# Sheet1.net
KiCad netlist of a schematic drawn in Altium Designer
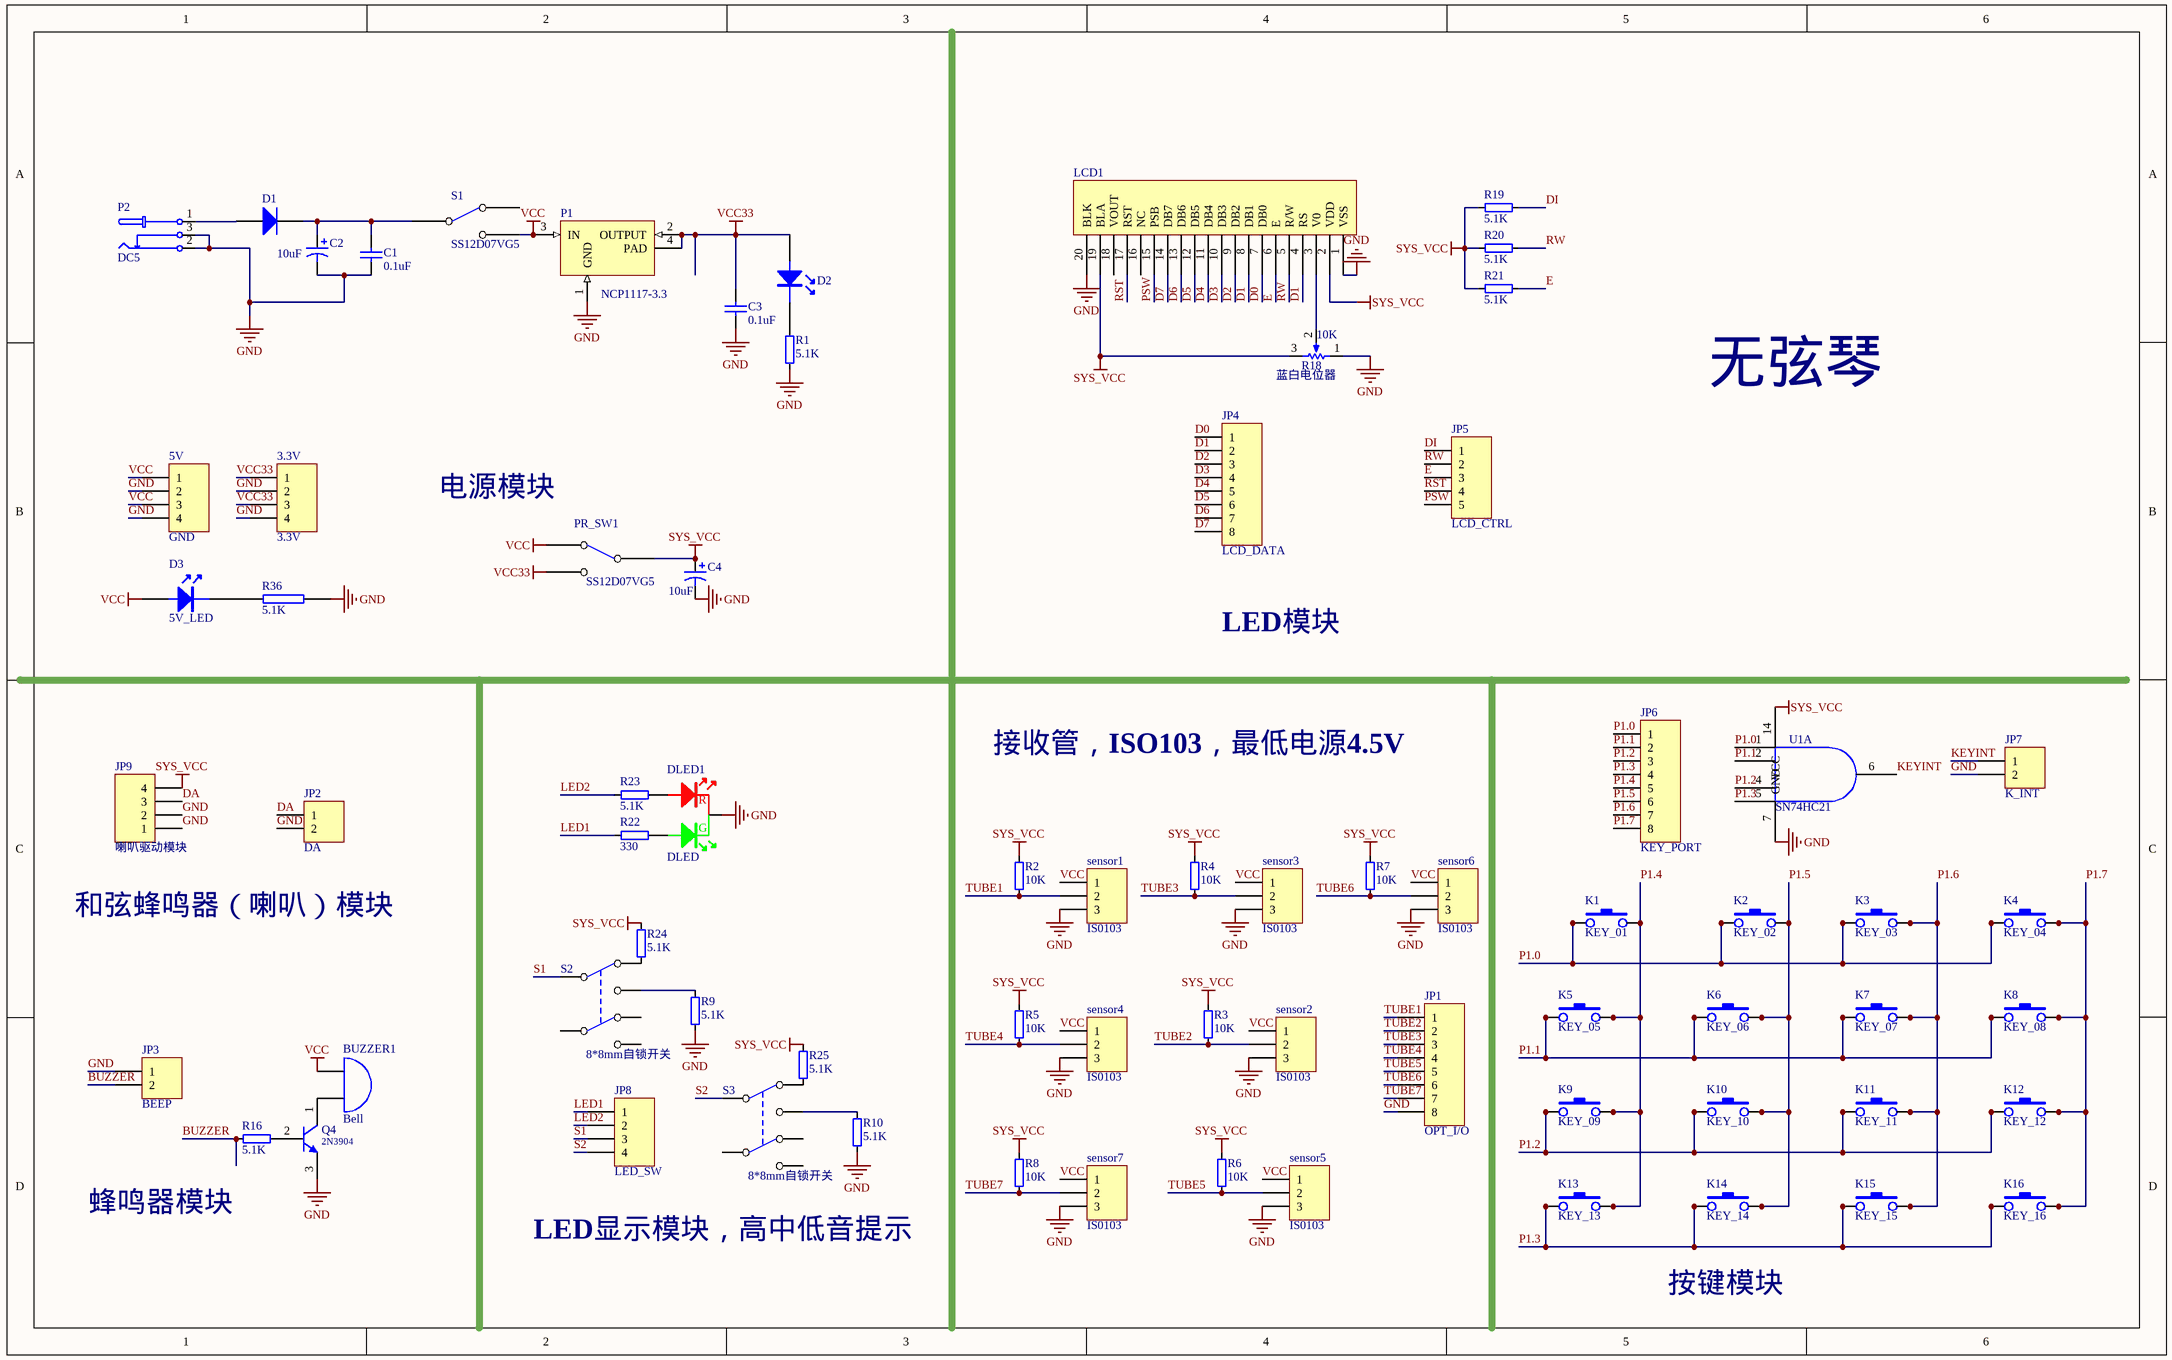
[diagram p0: Sheet1.SchDoc]

(export (version "E")
  (design (tool "Eeschema 10.0.6"))
  (components
    (comp (ref "3.3V")
      (value "3.3V")
      (footprint "HDR1X4")
      (description "Header, 4-Pin")
      (fields (field (name "PUBLISHER") "Altium Limited"))
      (libsource (lib "4. WXQv4") (part "Header 4"))
    )
    (comp (ref "5V")
      (value "GND")
      (footprint "HDR1X4")
      (description "Header, 4-Pin, Right Angle")
      (fields (field (name "PUBLISHER") "Altium Limited"))
      (libsource (lib "4. WXQv4") (part "Header 4H"))
    )
    (comp (ref "BUZZER1")
      (value "Bell")
      (footprint "BUZZER")
      (description "Electrical Bell")
      (fields (field (name "PUBLISHER") "Altium Limited"))
      (libsource (lib "4. WXQv4") (part "Bell"))
    )
    (comp (ref "C1")
      (value "0.1uF")
      (footprint "0805C")
      (description "Capacitor")
      (fields (field (name "PUBLISHER") "Altium Limited"))
      (libsource (lib "4. WXQv4") (part "Cap"))
    )
    (comp (ref "C2")
      (value "10uF")
      (footprint "1206C")
      (description "Polarized Capacitor (Radial)")
      (fields (field (name "PUBLISHER") "Altium Limited"))
      (libsource (lib "4. WXQv4") (part "Cap Pol1"))
    )
    (comp (ref "C3")
      (value "0.1uF")
      (footprint "0805C")
      (description "Capacitor")
      (fields (field (name "PUBLISHER") "Altium Limited"))
      (libsource (lib "4. WXQv4") (part "Cap"))
    )
    (comp (ref "C4")
      (value "10uF")
      (footprint "1206C")
      (description "Polarized Capacitor (Radial)")
      (fields (field (name "PUBLISHER") "Altium Limited"))
      (libsource (lib "4. WXQv4") (part "Cap Pol1"))
    )
    (comp (ref "D1")
      (value "1N4147")
      (footprint "DIODE0.3")
      (description "1 Amp General Purpose Rectifier")
      (fields (field (name "PUBLISHER") "Altium Limited"))
      (libsource (lib "4. WXQv4") (part "Diode 1N4007"))
    )
    (comp (ref "D2") (value "3.3V_LED") (footprint "LED0805") (libsource (lib "4. WXQv4") (part "LED_1")))
    (comp (ref "D3") (value "5V_LED") (footprint "LED0805") (libsource (lib "4. WXQv4") (part "LED_1")))
    (comp (ref "DLED1") (value "DLED") (footprint "DColor LED") (libsource (lib "4. WXQv4") (part "DLED")))
    (comp (ref "JP1")
      (value "OPT_I/O")
      (footprint "HDR1X8")
      (description "Header, 8-Pin")
      (fields (field (name "PUBLISHER") "Altium Limited"))
      (libsource (lib "4. WXQv4") (part "Header 8"))
    )
    (comp (ref "JP2")
      (value "DA")
      (footprint "HDR1X2")
      (description "Header, 2-Pin")
      (fields (field (name "PUBLISHER") "Altium Limited"))
      (libsource (lib "4. WXQv4") (part "Header 2"))
    )
    (comp (ref "JP3")
      (value "BEEP")
      (footprint "HDR1X2")
      (description "Header, 2-Pin")
      (fields (field (name "PUBLISHER") "Altium Limited"))
      (libsource (lib "4. WXQv4") (part "Header 2"))
    )
    (comp (ref "JP4")
      (value "LCD_DATA")
      (footprint "HDR1X8")
      (description "Header, 8-Pin")
      (fields (field (name "PUBLISHER") "Altium Limited"))
      (libsource (lib "4. WXQv4") (part "Header 8"))
    )
    (comp (ref "JP5")
      (value "LCD_CTRL")
      (footprint "HDR1X5")
      (description "Header, 5-Pin")
      (fields (field (name "PUBLISHER") "Altium Limited"))
      (libsource (lib "4. WXQv4") (part "Header 5"))
    )
    (comp (ref "JP6")
      (value "KEY_PORT")
      (footprint "HDR1X8")
      (description "Header, 8-Pin")
      (fields (field (name "PUBLISHER") "Altium Limited"))
      (libsource (lib "4. WXQv4") (part "Header 8"))
    )
    (comp (ref "JP7")
      (value "K_INT")
      (footprint "HDR1X2")
      (description "Header, 2-Pin, Right Angle")
      (fields (field (name "PUBLISHER") "Altium Limited"))
      (libsource (lib "4. WXQv4") (part "Header 2H"))
    )
    (comp (ref "JP8")
      (value "LED_SW")
      (footprint "HDR1X4")
      (description "Header, 4-Pin")
      (fields (field (name "PUBLISHER") "Altium Limited"))
      (libsource (lib "4. WXQv4") (part "Header 4"))
    )
    (comp (ref "JP9")
      (value "喇叭驱动模块")
      (footprint "HDR1X4")
      (description "Header, 4-Pin")
      (fields (field (name "PUBLISHER") "Altium Limited"))
      (libsource (lib "") (part "Header 4_1"))
    )
    (comp (ref "K1")
      (value "KEY_01")
      (footprint "DIP-6X6X5")
      (description "B3F-1055")
      (libsource (lib "4. WXQv4") (part "KEY"))
    )
    (comp (ref "K2")
      (value "KEY_02")
      (footprint "DIP-6X6X5")
      (description "B3F-1055")
      (libsource (lib "4. WXQv4") (part "KEY"))
    )
    (comp (ref "K3")
      (value "KEY_03")
      (footprint "DIP-6X6X5")
      (description "B3F-1055")
      (libsource (lib "4. WXQv4") (part "KEY"))
    )
    (comp (ref "K4")
      (value "KEY_04")
      (footprint "DIP-6X6X5")
      (description "B3F-1055")
      (libsource (lib "4. WXQv4") (part "KEY"))
    )
    (comp (ref "K5")
      (value "KEY_05")
      (footprint "DIP-6X6X5")
      (description "B3F-1055")
      (libsource (lib "4. WXQv4") (part "KEY"))
    )
    (comp (ref "K6")
      (value "KEY_06")
      (footprint "DIP-6X6X5")
      (description "B3F-1055")
      (libsource (lib "4. WXQv4") (part "KEY"))
    )
    (comp (ref "K7")
      (value "KEY_07")
      (footprint "DIP-6X6X5")
      (description "B3F-1055")
      (libsource (lib "4. WXQv4") (part "KEY"))
    )
    (comp (ref "K8")
      (value "KEY_08")
      (footprint "DIP-6X6X5")
      (description "B3F-1055")
      (libsource (lib "4. WXQv4") (part "KEY"))
    )
    (comp (ref "K9")
      (value "KEY_09")
      (footprint "DIP-6X6X5")
      (description "B3F-1055")
      (libsource (lib "4. WXQv4") (part "KEY"))
    )
    (comp (ref "K10")
      (value "KEY_10")
      (footprint "DIP-6X6X5")
      (description "B3F-1055")
      (libsource (lib "4. WXQv4") (part "KEY"))
    )
    (comp (ref "K11")
      (value "KEY_11")
      (footprint "DIP-6X6X5")
      (description "B3F-1055")
      (libsource (lib "4. WXQv4") (part "KEY"))
    )
    (comp (ref "K12")
      (value "KEY_12")
      (footprint "DIP-6X6X5")
      (description "B3F-1055")
      (libsource (lib "4. WXQv4") (part "KEY"))
    )
    (comp (ref "K13")
      (value "KEY_13")
      (footprint "DIP-6X6X5")
      (description "B3F-1055")
      (libsource (lib "4. WXQv4") (part "KEY"))
    )
    (comp (ref "K14")
      (value "KEY_14")
      (footprint "DIP-6X6X5")
      (description "B3F-1055")
      (libsource (lib "4. WXQv4") (part "KEY"))
    )
    (comp (ref "K15")
      (value "KEY_15")
      (footprint "DIP-6X6X5")
      (description "B3F-1055")
      (libsource (lib "4. WXQv4") (part "KEY"))
    )
    (comp (ref "K16")
      (value "KEY_16")
      (footprint "DIP-6X6X5")
      (description "B3F-1055")
      (libsource (lib "4. WXQv4") (part "KEY"))
    )
    (comp (ref "LCD1")
      (value "LCD")
      (footprint "HDR1X20")
      (libsource (lib "4. WXQv4") (part "COMPONENT_1_1"))
    )
    (comp (ref "P1") (value "NCP1117-3.3") (footprint "DPAK1") (libsource (lib "4. WXQv4") (part "NCP1117")))
    (comp (ref "P2")
      (value "DC5")
      (footprint "DC-005")
      (description "DC-005方口电源插座")
      (libsource (lib "4. WXQv4") (part "DC_Socket"))
    )
    (comp (ref "PR_SW1")
      (value "SS12D07VG5")
      (footprint "SS12D07VG3")
      (libsource (lib "4. WXQv4") (part "SW SPDT"))
    )
    (comp (ref "Q4")
      (value "2N3904")
      (footprint "TO-92A")
      (description "NPN General Purpose Amplifier")
      (fields (field (name "PUBLISHER") "Altium Limited"))
      (libsource (lib "4. WXQv4") (part "2N3904"))
    )
    (comp (ref "R1")
      (value "5.1K")
      (footprint "0805R")
      (description "resistor")
      (libsource (lib "4. WXQv4") (part "R-10K"))
    )
    (comp (ref "R2")
      (value "10K")
      (footprint "0805R")
      (description "resistor")
      (libsource (lib "4. WXQv4") (part "R-10K"))
    )
    (comp (ref "R3")
      (value "10K")
      (footprint "0805R")
      (description "resistor")
      (libsource (lib "4. WXQv4") (part "R-10K"))
    )
    (comp (ref "R4")
      (value "10K")
      (footprint "0805R")
      (description "resistor")
      (libsource (lib "4. WXQv4") (part "R-10K"))
    )
    (comp (ref "R5")
      (value "10K")
      (footprint "0805R")
      (description "resistor")
      (libsource (lib "4. WXQv4") (part "R-10K"))
    )
    (comp (ref "R6")
      (value "10K")
      (footprint "0805R")
      (description "resistor")
      (libsource (lib "4. WXQv4") (part "R-10K"))
    )
    (comp (ref "R7")
      (value "10K")
      (footprint "0805R")
      (description "resistor")
      (libsource (lib "4. WXQv4") (part "R-10K"))
    )
    (comp (ref "R8")
      (value "10K")
      (footprint "0805R")
      (description "resistor")
      (libsource (lib "4. WXQv4") (part "R-10K"))
    )
    (comp (ref "R9")
      (value "5.1K")
      (footprint "0805R")
      (description "resistor")
      (libsource (lib "4. WXQv4") (part "R-10K"))
    )
    (comp (ref "R10")
      (value "5.1K")
      (footprint "0805R")
      (description "resistor")
      (libsource (lib "4. WXQv4") (part "R-10K"))
    )
    (comp (ref "R16")
      (value "5.1K")
      (footprint "0805R")
      (description "resistor")
      (libsource (lib "4. WXQv4") (part "R-10K"))
    )
    (comp (ref "R18")
      (value "蓝白电位器")
      (footprint "RM065")
      (description "Potentiometer")
      (fields (field (name "ALTIUM_VALUE") "10K") (field (name "PUBLISHER") "Altium Limited"))
      (libsource (lib "4. WXQv4") (part "RPot"))
    )
    (comp (ref "R19")
      (value "5.1K")
      (footprint "0805R")
      (description "resistor")
      (libsource (lib "4. WXQv4") (part "R-10K"))
    )
    (comp (ref "R20")
      (value "5.1K")
      (footprint "0805R")
      (description "resistor")
      (libsource (lib "4. WXQv4") (part "R-10K"))
    )
    (comp (ref "R21")
      (value "5.1K")
      (footprint "0805R")
      (description "resistor")
      (libsource (lib "4. WXQv4") (part "R-10K"))
    )
    (comp (ref "R22")
      (value "330")
      (footprint "0805R")
      (description "resistor")
      (libsource (lib "4. WXQv4") (part "R-10K"))
    )
    (comp (ref "R23")
      (value "5.1K")
      (footprint "0805R")
      (description "resistor")
      (libsource (lib "4. WXQv4") (part "R-10K"))
    )
    (comp (ref "R24")
      (value "5.1K")
      (footprint "0805R")
      (description "resistor")
      (libsource (lib "4. WXQv4") (part "R-10K"))
    )
    (comp (ref "R25")
      (value "5.1K")
      (footprint "0805R")
      (description "resistor")
      (libsource (lib "4. WXQv4") (part "R-10K"))
    )
    (comp (ref "R36") (value "5.1K") (footprint "0805R") (libsource (lib "4. WXQv4") (part "RES2")))
    (comp (ref "S1")
      (value "SS12D07VG5")
      (footprint "SS12D07VG3")
      (libsource (lib "4. WXQv4") (part "SW SPDT"))
    )
    (comp (ref "S2")
      (value "8*8mm自锁开关")
      (footprint "KFT DIP-8X8")
      (libsource (lib "4. WXQv4") (part "KFT DIP-8X8"))
    )
    (comp (ref "S3")
      (value "8*8mm自锁开关")
      (footprint "KFT DIP-8X8")
      (libsource (lib "4. WXQv4") (part "KFT DIP-8X8"))
    )
    (comp (ref "sensor1")
      (value "IS0103")
      (footprint "IS0103")
      (description "Header, 3-Pin")
      (fields (field (name "PUBLISHER") "Altium Limited"))
      (libsource (lib "4. WXQv4") (part "Header 3"))
    )
    (comp (ref "sensor2")
      (value "IS0103")
      (footprint "IS0103")
      (description "Header, 3-Pin")
      (fields (field (name "PUBLISHER") "Altium Limited"))
      (libsource (lib "4. WXQv4") (part "Header 3"))
    )
    (comp (ref "sensor3")
      (value "IS0103")
      (footprint "IS0103")
      (description "Header, 3-Pin")
      (fields (field (name "PUBLISHER") "Altium Limited"))
      (libsource (lib "4. WXQv4") (part "Header 3"))
    )
    (comp (ref "sensor4")
      (value "IS0103")
      (footprint "IS0103")
      (description "Header, 3-Pin")
      (fields (field (name "PUBLISHER") "Altium Limited"))
      (libsource (lib "4. WXQv4") (part "Header 3"))
    )
    (comp (ref "sensor5")
      (value "IS0103")
      (footprint "IS0103")
      (description "Header, 3-Pin")
      (fields (field (name "PUBLISHER") "Altium Limited"))
      (libsource (lib "4. WXQv4") (part "Header 3"))
    )
    (comp (ref "sensor6")
      (value "IS0103")
      (footprint "IS0103")
      (description "Header, 3-Pin")
      (fields (field (name "PUBLISHER") "Altium Limited"))
      (libsource (lib "4. WXQv4") (part "Header 3"))
    )
    (comp (ref "sensor7")
      (value "IS0103")
      (footprint "IS0103")
      (description "Header, 3-Pin")
      (fields (field (name "PUBLISHER") "Altium Limited"))
      (libsource (lib "4. WXQv4") (part "Header 3"))
    )
    (comp (ref "U1A") (value "SN74HC21") (footprint "74HC21D") (libsource (lib "4. WXQv4") (part "74HC21")))
  )
  (nets
    (net (code "1") (name "/BUZZER") (class "Default")
      (node (ref "JP3") (pin "2") (pinfunction "2_2") (pintype "passive"))
      (node (ref "R16") (pin "1") (pinfunction "1_1") (pintype "passive"))
    )
    (net (code "2") (name "/D0") (class "Default")
      (node (ref "JP4") (pin "1") (pinfunction "1_1") (pintype "passive"))
      (node (ref "LCD1") (pin "7") (pinfunction "DB0_7") (pintype "passive"))
    )
    (net (code "3") (name "/D1") (class "Default")
      (node (ref "JP4") (pin "2") (pinfunction "2_2") (pintype "passive"))
      (node (ref "LCD1") (pin "4") (pinfunction "RS_4") (pintype "passive"))
      (node (ref "LCD1") (pin "8") (pinfunction "DB1_8") (pintype "passive"))
    )
    (net (code "4") (name "/D2") (class "Default")
      (node (ref "JP4") (pin "3") (pinfunction "3_3") (pintype "passive"))
      (node (ref "LCD1") (pin "9") (pinfunction "DB2_9") (pintype "passive"))
    )
    (net (code "5") (name "/D3") (class "Default")
      (node (ref "JP4") (pin "4") (pinfunction "4_4") (pintype "passive"))
      (node (ref "LCD1") (pin "10") (pinfunction "DB3_10") (pintype "passive"))
    )
    (net (code "6") (name "/D4") (class "Default")
      (node (ref "JP4") (pin "5") (pinfunction "5_5") (pintype "passive"))
      (node (ref "LCD1") (pin "11") (pinfunction "DB4_11") (pintype "passive"))
    )
    (net (code "7") (name "/D5") (class "Default")
      (node (ref "JP4") (pin "6") (pinfunction "6_6") (pintype "passive"))
      (node (ref "LCD1") (pin "12") (pinfunction "DB5_12") (pintype "passive"))
    )
    (net (code "8") (name "/D6") (class "Default")
      (node (ref "JP4") (pin "7") (pinfunction "7_7") (pintype "passive"))
      (node (ref "LCD1") (pin "13") (pinfunction "DB6_13") (pintype "passive"))
    )
    (net (code "9") (name "/D7") (class "Default")
      (node (ref "JP4") (pin "8") (pinfunction "8_8") (pintype "passive"))
      (node (ref "LCD1") (pin "14") (pinfunction "DB7_14") (pintype "passive"))
    )
    (net (code "10") (name "/DA") (class "Default")
      (node (ref "JP2") (pin "1") (pinfunction "1_1") (pintype "passive"))
      (node (ref "JP9") (pin "3") (pinfunction "3_3") (pintype "passive"))
    )
    (net (code "11") (name "/DI") (class "Default")
      (node (ref "JP5") (pin "1") (pinfunction "1_1") (pintype "passive"))
      (node (ref "R19") (pin "2") (pinfunction "2_2") (pintype "passive"))
    )
    (net (code "12") (name "/E") (class "Default")
      (node (ref "JP5") (pin "3") (pinfunction "3_3") (pintype "passive"))
      (node (ref "LCD1") (pin "6") (pinfunction "E_6") (pintype "passive"))
      (node (ref "R21") (pin "2") (pinfunction "2_2") (pintype "passive"))
    )
    (net (code "13") (name "/KEYINT") (class "Default")
      (node (ref "JP7") (pin "1") (pinfunction "1_1") (pintype "passive"))
      (node (ref "U1A") (pin "6") (pinfunction "6_6") (pintype "passive"))
    )
    (net (code "14") (name "/LED1") (class "Default")
      (node (ref "JP8") (pin "1") (pinfunction "1_1") (pintype "passive"))
      (node (ref "R22") (pin "1") (pinfunction "1_1") (pintype "passive"))
    )
    (net (code "15") (name "/LED2") (class "Default")
      (node (ref "JP8") (pin "2") (pinfunction "2_2") (pintype "passive"))
      (node (ref "R23") (pin "1") (pinfunction "1_1") (pintype "passive"))
    )
    (net (code "16") (name "/P1.0") (class "Default")
      (node (ref "JP6") (pin "1") (pinfunction "1_1") (pintype "passive"))
      (node (ref "K1") (pin "3") (pinfunction "3_3") (pintype "passive"))
      (node (ref "K1") (pin "4") (pinfunction "4_4") (pintype "passive"))
      (node (ref "K2") (pin "3") (pinfunction "3_3") (pintype "passive"))
      (node (ref "K2") (pin "4") (pinfunction "4_4") (pintype "passive"))
      (node (ref "K3") (pin "3") (pinfunction "3_3") (pintype "passive"))
      (node (ref "K3") (pin "4") (pinfunction "4_4") (pintype "passive"))
      (node (ref "K4") (pin "3") (pinfunction "3_3") (pintype "passive"))
      (node (ref "K4") (pin "4") (pinfunction "4_4") (pintype "passive"))
      (node (ref "U1A") (pin "1") (pinfunction "1_1") (pintype "passive"))
    )
    (net (code "17") (name "/P1.1") (class "Default")
      (node (ref "JP6") (pin "2") (pinfunction "2_2") (pintype "passive"))
      (node (ref "K5") (pin "3") (pinfunction "3_3") (pintype "passive"))
      (node (ref "K5") (pin "4") (pinfunction "4_4") (pintype "passive"))
      (node (ref "K6") (pin "3") (pinfunction "3_3") (pintype "passive"))
      (node (ref "K6") (pin "4") (pinfunction "4_4") (pintype "passive"))
      (node (ref "K7") (pin "3") (pinfunction "3_3") (pintype "passive"))
      (node (ref "K7") (pin "4") (pinfunction "4_4") (pintype "passive"))
      (node (ref "K8") (pin "3") (pinfunction "3_3") (pintype "passive"))
      (node (ref "K8") (pin "4") (pinfunction "4_4") (pintype "passive"))
      (node (ref "U1A") (pin "2") (pinfunction "2_2") (pintype "passive"))
    )
    (net (code "18") (name "/P1.2") (class "Default")
      (node (ref "JP6") (pin "3") (pinfunction "3_3") (pintype "passive"))
      (node (ref "K10") (pin "3") (pinfunction "3_3") (pintype "passive"))
      (node (ref "K10") (pin "4") (pinfunction "4_4") (pintype "passive"))
      (node (ref "K11") (pin "3") (pinfunction "3_3") (pintype "passive"))
      (node (ref "K11") (pin "4") (pinfunction "4_4") (pintype "passive"))
      (node (ref "K12") (pin "3") (pinfunction "3_3") (pintype "passive"))
      (node (ref "K12") (pin "4") (pinfunction "4_4") (pintype "passive"))
      (node (ref "K9") (pin "3") (pinfunction "3_3") (pintype "passive"))
      (node (ref "K9") (pin "4") (pinfunction "4_4") (pintype "passive"))
      (node (ref "U1A") (pin "4") (pinfunction "4_4") (pintype "passive"))
    )
    (net (code "19") (name "/P1.3") (class "Default")
      (node (ref "JP6") (pin "4") (pinfunction "4_4") (pintype "passive"))
      (node (ref "K13") (pin "3") (pinfunction "3_3") (pintype "passive"))
      (node (ref "K13") (pin "4") (pinfunction "4_4") (pintype "passive"))
      (node (ref "K14") (pin "3") (pinfunction "3_3") (pintype "passive"))
      (node (ref "K14") (pin "4") (pinfunction "4_4") (pintype "passive"))
      (node (ref "K15") (pin "3") (pinfunction "3_3") (pintype "passive"))
      (node (ref "K15") (pin "4") (pinfunction "4_4") (pintype "passive"))
      (node (ref "K16") (pin "3") (pinfunction "3_3") (pintype "passive"))
      (node (ref "K16") (pin "4") (pinfunction "4_4") (pintype "passive"))
      (node (ref "U1A") (pin "5") (pinfunction "5_5") (pintype "passive"))
    )
    (net (code "20") (name "/P1.4") (class "Default")
      (node (ref "JP6") (pin "5") (pinfunction "5_5") (pintype "passive"))
      (node (ref "K1") (pin "1") (pinfunction "1_1") (pintype "passive"))
      (node (ref "K1") (pin "2") (pinfunction "2_2") (pintype "passive"))
      (node (ref "K13") (pin "1") (pinfunction "1_1") (pintype "passive"))
      (node (ref "K13") (pin "2") (pinfunction "2_2") (pintype "passive"))
      (node (ref "K5") (pin "1") (pinfunction "1_1") (pintype "passive"))
      (node (ref "K5") (pin "2") (pinfunction "2_2") (pintype "passive"))
      (node (ref "K9") (pin "1") (pinfunction "1_1") (pintype "passive"))
      (node (ref "K9") (pin "2") (pinfunction "2_2") (pintype "passive"))
    )
    (net (code "21") (name "/P1.5") (class "Default")
      (node (ref "JP6") (pin "6") (pinfunction "6_6") (pintype "passive"))
      (node (ref "K10") (pin "1") (pinfunction "1_1") (pintype "passive"))
      (node (ref "K10") (pin "2") (pinfunction "2_2") (pintype "passive"))
      (node (ref "K14") (pin "1") (pinfunction "1_1") (pintype "passive"))
      (node (ref "K14") (pin "2") (pinfunction "2_2") (pintype "passive"))
      (node (ref "K2") (pin "1") (pinfunction "1_1") (pintype "passive"))
      (node (ref "K2") (pin "2") (pinfunction "2_2") (pintype "passive"))
      (node (ref "K6") (pin "1") (pinfunction "1_1") (pintype "passive"))
      (node (ref "K6") (pin "2") (pinfunction "2_2") (pintype "passive"))
    )
    (net (code "22") (name "/P1.6") (class "Default")
      (node (ref "JP6") (pin "7") (pinfunction "7_7") (pintype "passive"))
      (node (ref "K11") (pin "1") (pinfunction "1_1") (pintype "passive"))
      (node (ref "K11") (pin "2") (pinfunction "2_2") (pintype "passive"))
      (node (ref "K15") (pin "1") (pinfunction "1_1") (pintype "passive"))
      (node (ref "K15") (pin "2") (pinfunction "2_2") (pintype "passive"))
      (node (ref "K3") (pin "1") (pinfunction "1_1") (pintype "passive"))
      (node (ref "K3") (pin "2") (pinfunction "2_2") (pintype "passive"))
      (node (ref "K7") (pin "1") (pinfunction "1_1") (pintype "passive"))
      (node (ref "K7") (pin "2") (pinfunction "2_2") (pintype "passive"))
    )
    (net (code "23") (name "/P1.7") (class "Default")
      (node (ref "JP6") (pin "8") (pinfunction "8_8") (pintype "passive"))
      (node (ref "K12") (pin "1") (pinfunction "1_1") (pintype "passive"))
      (node (ref "K12") (pin "2") (pinfunction "2_2") (pintype "passive"))
      (node (ref "K16") (pin "1") (pinfunction "1_1") (pintype "passive"))
      (node (ref "K16") (pin "2") (pinfunction "2_2") (pintype "passive"))
      (node (ref "K4") (pin "1") (pinfunction "1_1") (pintype "passive"))
      (node (ref "K4") (pin "2") (pinfunction "2_2") (pintype "passive"))
      (node (ref "K8") (pin "1") (pinfunction "1_1") (pintype "passive"))
      (node (ref "K8") (pin "2") (pinfunction "2_2") (pintype "passive"))
    )
    (net (code "24") (name "/PSW") (class "Default")
      (node (ref "JP5") (pin "5") (pinfunction "5_5") (pintype "passive"))
      (node (ref "LCD1") (pin "15") (pinfunction "PSB_15") (pintype "passive"))
    )
    (net (code "25") (name "/RST") (class "Default")
      (node (ref "JP5") (pin "4") (pinfunction "4_4") (pintype "passive"))
      (node (ref "LCD1") (pin "17") (pinfunction "RST_17") (pintype "passive"))
    )
    (net (code "26") (name "/RW") (class "Default")
      (node (ref "JP5") (pin "2") (pinfunction "2_2") (pintype "passive"))
      (node (ref "LCD1") (pin "5") (pinfunction "R/W_5") (pintype "passive"))
      (node (ref "R20") (pin "2") (pinfunction "2_2") (pintype "passive"))
    )
    (net (code "27") (name "/S1") (class "Default")
      (node (ref "JP8") (pin "3") (pinfunction "3_3") (pintype "passive"))
      (node (ref "S2") (pin "2") (pinfunction "2_2") (pintype "passive"))
    )
    (net (code "28") (name "/S2") (class "Default")
      (node (ref "JP8") (pin "4") (pinfunction "4_4") (pintype "passive"))
      (node (ref "S3") (pin "2") (pinfunction "2_2") (pintype "passive"))
    )
    (net (code "29") (name "/TUBE1") (class "Default")
      (node (ref "JP1") (pin "1") (pinfunction "1_1") (pintype "passive"))
      (node (ref "R2") (pin "1") (pinfunction "1_1") (pintype "passive"))
      (node (ref "sensor1") (pin "2") (pinfunction "2_2") (pintype "passive"))
    )
    (net (code "30") (name "/TUBE2") (class "Default")
      (node (ref "JP1") (pin "2") (pinfunction "2_2") (pintype "passive"))
      (node (ref "R3") (pin "1") (pinfunction "1_1") (pintype "passive"))
      (node (ref "sensor2") (pin "2") (pinfunction "2_2") (pintype "passive"))
    )
    (net (code "31") (name "/TUBE3") (class "Default")
      (node (ref "JP1") (pin "3") (pinfunction "3_3") (pintype "passive"))
      (node (ref "R4") (pin "1") (pinfunction "1_1") (pintype "passive"))
      (node (ref "sensor3") (pin "2") (pinfunction "2_2") (pintype "passive"))
    )
    (net (code "32") (name "/TUBE4") (class "Default")
      (node (ref "JP1") (pin "4") (pinfunction "4_4") (pintype "passive"))
      (node (ref "R5") (pin "1") (pinfunction "1_1") (pintype "passive"))
      (node (ref "sensor4") (pin "2") (pinfunction "2_2") (pintype "passive"))
    )
    (net (code "33") (name "/TUBE5") (class "Default")
      (node (ref "JP1") (pin "5") (pinfunction "5_5") (pintype "passive"))
      (node (ref "R6") (pin "1") (pinfunction "1_1") (pintype "passive"))
      (node (ref "sensor5") (pin "2") (pinfunction "2_2") (pintype "passive"))
    )
    (net (code "34") (name "/TUBE6") (class "Default")
      (node (ref "JP1") (pin "6") (pinfunction "6_6") (pintype "passive"))
      (node (ref "R7") (pin "1") (pinfunction "1_1") (pintype "passive"))
      (node (ref "sensor6") (pin "2") (pinfunction "2_2") (pintype "passive"))
    )
    (net (code "35") (name "/TUBE7") (class "Default")
      (node (ref "JP1") (pin "7") (pinfunction "7_7") (pintype "passive"))
      (node (ref "R8") (pin "1") (pinfunction "1_1") (pintype "passive"))
      (node (ref "sensor7") (pin "2") (pinfunction "2_2") (pintype "passive"))
    )
    (net (code "36") (name "GND") (class "Default")
      (node (ref "3.3V") (pin "2") (pinfunction "2_2") (pintype "passive"))
      (node (ref "3.3V") (pin "4") (pinfunction "4_4") (pintype "passive"))
      (node (ref "5V") (pin "2") (pinfunction "2_2") (pintype "passive"))
      (node (ref "5V") (pin "4") (pinfunction "4_4") (pintype "passive"))
      (node (ref "C1") (pin "1") (pinfunction "1_1") (pintype "passive"))
      (node (ref "C2") (pin "2") (pinfunction "2_2") (pintype "passive"))
      (node (ref "C3") (pin "1") (pinfunction "1_1") (pintype "passive"))
      (node (ref "C4") (pin "2") (pinfunction "2_2") (pintype "passive"))
      (node (ref "DLED1") (pin "1") (pinfunction "C_1") (pintype "passive"))
      (node (ref "JP1") (pin "8") (pinfunction "8_8") (pintype "passive"))
      (node (ref "JP2") (pin "2") (pinfunction "2_2") (pintype "passive"))
      (node (ref "JP3") (pin "1") (pinfunction "1_1") (pintype "passive"))
      (node (ref "JP7") (pin "2") (pinfunction "2_2") (pintype "passive"))
      (node (ref "JP9") (pin "1") (pinfunction "1_1") (pintype "passive"))
      (node (ref "JP9") (pin "2") (pinfunction "2_2") (pintype "passive"))
      (node (ref "LCD1") (pin "1") (pinfunction "VSS_1") (pintype "passive"))
      (node (ref "LCD1") (pin "20") (pinfunction "BLK_20") (pintype "passive"))
      (node (ref "P1") (pin "1") (pinfunction "GND_1") (pintype "input"))
      (node (ref "P2") (pin "2") (pinfunction "2_2") (pintype "passive"))
      (node (ref "P2") (pin "3") (pinfunction "3_3") (pintype "passive"))
      (node (ref "Q4") (pin "3") (pinfunction "E_3") (pintype "passive"))
      (node (ref "R1") (pin "1") (pinfunction "1_1") (pintype "passive"))
      (node (ref "R10") (pin "1") (pinfunction "1_1") (pintype "passive"))
      (node (ref "R18") (pin "1") (pinfunction "TOP_1") (pintype "passive"))
      (node (ref "R36") (pin "2") (pinfunction "2_2") (pintype "passive"))
      (node (ref "R9") (pin "1") (pinfunction "1_1") (pintype "passive"))
      (node (ref "U1A") (pin "7") (pinfunction "GND_7") (pintype "passive"))
      (node (ref "sensor1") (pin "3") (pinfunction "3_3") (pintype "passive"))
      (node (ref "sensor2") (pin "3") (pinfunction "3_3") (pintype "passive"))
      (node (ref "sensor3") (pin "3") (pinfunction "3_3") (pintype "passive"))
      (node (ref "sensor4") (pin "3") (pinfunction "3_3") (pintype "passive"))
      (node (ref "sensor5") (pin "3") (pinfunction "3_3") (pintype "passive"))
      (node (ref "sensor6") (pin "3") (pinfunction "3_3") (pintype "passive"))
      (node (ref "sensor7") (pin "3") (pinfunction "3_3") (pintype "passive"))
    )
    (net (code "37") (name "Net-(BUZZER1-B)") (class "Default")
      (node (ref "BUZZER1") (pin "2") (pinfunction "B_2") (pintype "passive"))
      (node (ref "Q4") (pin "1") (pinfunction "C_1") (pintype "passive"))
    )
    (net (code "38") (name "Net-(D1-A)") (class "Default")
      (node (ref "D1") (pin "1") (pinfunction "A_1") (pintype "passive"))
      (node (ref "P2") (pin "1") (pinfunction "1_1") (pintype "passive"))
    )
    (net (code "39") (name "Net-(D1-K)") (class "Default")
      (node (ref "C1") (pin "2") (pinfunction "2_2") (pintype "passive"))
      (node (ref "C2") (pin "1") (pinfunction "1_1") (pintype "passive"))
      (node (ref "D1") (pin "2") (pinfunction "K_2") (pintype "passive"))
      (node (ref "S1") (pin "2") (pinfunction "COMMON_2") (pintype "passive"))
    )
    (net (code "40") (name "Net-(D2-Pad2)") (class "Default")
      (node (ref "D2") (pin "2") (pinfunction "2_2") (pintype "passive"))
      (node (ref "R1") (pin "2") (pinfunction "2_2") (pintype "passive"))
    )
    (net (code "41") (name "Net-(D3-Pad2)") (class "Default")
      (node (ref "D3") (pin "2") (pinfunction "2_2") (pintype "passive"))
      (node (ref "R36") (pin "1") (pinfunction "1_1") (pintype "passive"))
    )
    (net (code "42") (name "Net-(DLED1-G)") (class "Default")
      (node (ref "DLED1") (pin "2") (pinfunction "G_2") (pintype "passive"))
      (node (ref "R22") (pin "2") (pinfunction "2_2") (pintype "passive"))
    )
    (net (code "43") (name "Net-(DLED1-R)") (class "Default")
      (node (ref "DLED1") (pin "3") (pinfunction "R_3") (pintype "passive"))
      (node (ref "R23") (pin "2") (pinfunction "2_2") (pintype "passive"))
    )
    (net (code "44") (name "Net-(LCD1-V0)") (class "Default")
      (node (ref "LCD1") (pin "3") (pinfunction "V0_3") (pintype "passive"))
      (node (ref "R18") (pin "2") (pintype "passive"))
    )
    (net (code "45") (name "Net-(Q4-B)") (class "Default")
      (node (ref "Q4") (pin "2") (pinfunction "B_2") (pintype "passive"))
      (node (ref "R16") (pin "2") (pinfunction "2_2") (pintype "passive"))
    )
    (net (code "46") (name "Net-(R9-Pad2)") (class "Default")
      (node (ref "R9") (pin "2") (pinfunction "2_2") (pintype "passive"))
      (node (ref "S2") (pin "1") (pinfunction "1_1") (pintype "passive"))
    )
    (net (code "47") (name "Net-(R10-Pad2)") (class "Default")
      (node (ref "R10") (pin "2") (pinfunction "2_2") (pintype "passive"))
      (node (ref "S3") (pin "1") (pinfunction "1_1") (pintype "passive"))
    )
    (net (code "48") (name "Net-(R24-Pad1)") (class "Default")
      (node (ref "R24") (pin "1") (pinfunction "1_1") (pintype "passive"))
      (node (ref "S2") (pin "3") (pinfunction "3_3") (pintype "passive"))
    )
    (net (code "49") (name "Net-(R25-Pad1)") (class "Default")
      (node (ref "R25") (pin "1") (pinfunction "1_1") (pintype "passive"))
      (node (ref "S3") (pin "3") (pinfunction "3_3") (pintype "passive"))
    )
    (net (code "50") (name "SYS_VCC") (class "Default")
      (node (ref "C4") (pin "1") (pinfunction "1_1") (pintype "passive"))
      (node (ref "JP9") (pin "4") (pinfunction "4_4") (pintype "passive"))
      (node (ref "LCD1") (pin "19") (pinfunction "BLA_19") (pintype "passive"))
      (node (ref "LCD1") (pin "2") (pinfunction "VDD_2") (pintype "passive"))
      (node (ref "PR_SW1") (pin "2") (pinfunction "COMMON_2") (pintype "passive"))
      (node (ref "R18") (pin "3") (pintype "passive"))
      (node (ref "R19") (pin "1") (pinfunction "1_1") (pintype "passive"))
      (node (ref "R2") (pin "2") (pinfunction "2_2") (pintype "passive"))
      (node (ref "R20") (pin "1") (pinfunction "1_1") (pintype "passive"))
      (node (ref "R21") (pin "1") (pinfunction "1_1") (pintype "passive"))
      (node (ref "R24") (pin "2") (pinfunction "2_2") (pintype "passive"))
      (node (ref "R25") (pin "2") (pinfunction "2_2") (pintype "passive"))
      (node (ref "R3") (pin "2") (pinfunction "2_2") (pintype "passive"))
      (node (ref "R4") (pin "2") (pinfunction "2_2") (pintype "passive"))
      (node (ref "R5") (pin "2") (pinfunction "2_2") (pintype "passive"))
      (node (ref "R6") (pin "2") (pinfunction "2_2") (pintype "passive"))
      (node (ref "R7") (pin "2") (pinfunction "2_2") (pintype "passive"))
      (node (ref "R8") (pin "2") (pinfunction "2_2") (pintype "passive"))
      (node (ref "U1A") (pin "14") (pinfunction "VCC_14") (pintype "passive"))
    )
    (net (code "51") (name "VCC") (class "Default")
      (node (ref "5V") (pin "1") (pinfunction "1_1") (pintype "passive"))
      (node (ref "5V") (pin "3") (pinfunction "3_3") (pintype "passive"))
      (node (ref "BUZZER1") (pin "1") (pinfunction "A_1") (pintype "passive"))
      (node (ref "D3") (pin "1") (pinfunction "1_1") (pintype "passive"))
      (node (ref "P1") (pin "3") (pinfunction "IN_3") (pintype "input"))
      (node (ref "PR_SW1") (pin "1") (pinfunction "NC_1") (pintype "passive"))
      (node (ref "S1") (pin "3") (pinfunction "NO_3") (pintype "passive"))
      (node (ref "sensor1") (pin "1") (pinfunction "1_1") (pintype "passive"))
      (node (ref "sensor2") (pin "1") (pinfunction "1_1") (pintype "passive"))
      (node (ref "sensor3") (pin "1") (pinfunction "1_1") (pintype "passive"))
      (node (ref "sensor4") (pin "1") (pinfunction "1_1") (pintype "passive"))
      (node (ref "sensor5") (pin "1") (pinfunction "1_1") (pintype "passive"))
      (node (ref "sensor6") (pin "1") (pinfunction "1_1") (pintype "passive"))
      (node (ref "sensor7") (pin "1") (pinfunction "1_1") (pintype "passive"))
    )
    (net (code "52") (name "VCC33") (class "Default")
      (node (ref "3.3V") (pin "1") (pinfunction "1_1") (pintype "passive"))
      (node (ref "3.3V") (pin "3") (pinfunction "3_3") (pintype "passive"))
      (node (ref "C3") (pin "2") (pinfunction "2_2") (pintype "passive"))
      (node (ref "D2") (pin "1") (pinfunction "1_1") (pintype "passive"))
      (node (ref "P1") (pin "2") (pinfunction "OUTPUT_2") (pintype "input"))
      (node (ref "P1") (pin "4") (pinfunction "PAD_4") (pintype "passive"))
      (node (ref "PR_SW1") (pin "3") (pinfunction "NO_3") (pintype "passive"))
    )
    (net (code "53") (name "unconnected-(LCD1-NC-Pad16)") (class "Default")
      (node (ref "LCD1") (pin "16") (pinfunction "NC_16") (pintype "passive"))
    )
    (net (code "54") (name "unconnected-(LCD1-VOUT-Pad18)") (class "Default")
      (node (ref "LCD1") (pin "18") (pinfunction "VOUT_18") (pintype "passive"))
    )
    (net (code "55") (name "unconnected-(S1-NC-Pad1)") (class "Default")
      (node (ref "S1") (pin "1") (pinfunction "NC_1") (pintype "passive"))
    )
    (net (code "56") (name "unconnected-(S2-Pad4)") (class "Default")
      (node (ref "S2") (pin "4") (pinfunction "4_4") (pintype "passive"))
    )
    (net (code "57") (name "unconnected-(S2-Pad5)") (class "Default")
      (node (ref "S2") (pin "5") (pinfunction "5_5") (pintype "passive"))
    )
    (net (code "58") (name "unconnected-(S2-Pad6)") (class "Default")
      (node (ref "S2") (pin "6") (pinfunction "6_6") (pintype "passive"))
    )
    (net (code "59") (name "unconnected-(S3-Pad4)") (class "Default")
      (node (ref "S3") (pin "4") (pinfunction "4_4") (pintype "passive"))
    )
    (net (code "60") (name "unconnected-(S3-Pad5)") (class "Default")
      (node (ref "S3") (pin "5") (pinfunction "5_5") (pintype "passive"))
    )
    (net (code "61") (name "unconnected-(S3-Pad6)") (class "Default")
      (node (ref "S3") (pin "6") (pinfunction "6_6") (pintype "passive"))
    )
  )
)
